# wifiweatherguy.net
KiCad netlist of a schematic drawn in EAGLE
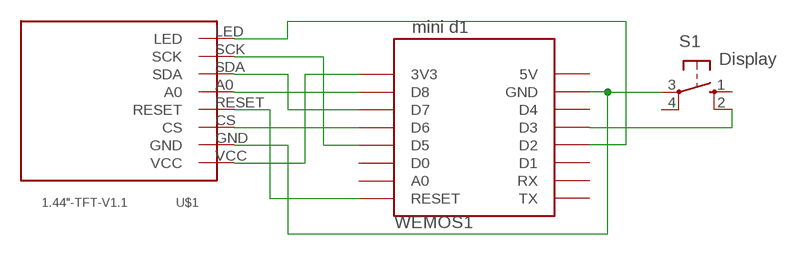
[diagram p0: schematic, sheet 1]

(export (version "E")
  (design (tool "Eeschema 10.0.6"))
  (components
    (comp (ref "S1")
      (value "Display")
      (footprint "eagle-import:B3F-10XX")
      (fields (field (name "MPN") "B3F-1000"))
      (libsource (lib "eagle-import") (part "10-XX"))
    )
    (comp (ref "U$1")
      (value "1.44\"-TFT-V1.1")
      (footprint "eagle-import:1.44-TFT-V1.1")
      (libsource (lib "eagle-import") (part "1.44{dblquote}-TFT-V1.1"))
    )
    (comp (ref "WEMOS1")
      (value "mini d1")
      (footprint "eagle-import:WEMOS-D1-MINI")
      (libsource (lib "eagle-import") (part "WEMOS-D1-MINI"))
    )
  )
  (nets
    (net (code "1") (name "Net-(S1-P)") (class "Default")
      (node (ref "S1") (pin "3") (pinfunction "P_3") (pintype "passive"))
      (node (ref "U$1") (pin "GND") (pinfunction "GND_GND") (pintype "bidirectional"))
      (node (ref "WEMOS1") (pin "GND") (pinfunction "GND_GND") (pintype "bidirectional"))
    )
    (net (code "2") (name "Net-(S1-S1)") (class "Default")
      (node (ref "S1") (pin "2") (pinfunction "S1_2") (pintype "passive"))
      (node (ref "WEMOS1") (pin "D3") (pinfunction "D3_D3") (pintype "bidirectional"))
    )
    (net (code "3") (name "Net-(U$1-PadA0)") (class "Default")
      (node (ref "U$1") (pin "A0") (pinfunction "A0_A0") (pintype "bidirectional"))
      (node (ref "WEMOS1") (pin "D8") (pinfunction "D8_D8") (pintype "bidirectional"))
    )
    (net (code "4") (name "Net-(U$1-PadCS)") (class "Default")
      (node (ref "U$1") (pin "CS") (pinfunction "CS_CS") (pintype "bidirectional"))
      (node (ref "WEMOS1") (pin "D6") (pinfunction "D6_D6") (pintype "bidirectional"))
    )
    (net (code "5") (name "Net-(U$1-PadLED)") (class "Default")
      (node (ref "U$1") (pin "LED") (pinfunction "LED_LED") (pintype "bidirectional"))
      (node (ref "WEMOS1") (pin "D2") (pinfunction "D2_D2") (pintype "bidirectional"))
    )
    (net (code "6") (name "Net-(U$1-PadRESET)") (class "Default")
      (node (ref "U$1") (pin "RESET") (pinfunction "RESET_RESET") (pintype "bidirectional"))
      (node (ref "WEMOS1") (pin "RESET") (pinfunction "RESET_RESET") (pintype "bidirectional"))
    )
    (net (code "7") (name "Net-(U$1-PadSCK)") (class "Default")
      (node (ref "U$1") (pin "SCK") (pinfunction "SCK_SCK") (pintype "bidirectional"))
      (node (ref "WEMOS1") (pin "D5") (pinfunction "D5_D5") (pintype "bidirectional"))
    )
    (net (code "8") (name "Net-(U$1-PadSDA)") (class "Default")
      (node (ref "U$1") (pin "SDA") (pinfunction "SDA_SDA") (pintype "bidirectional"))
      (node (ref "WEMOS1") (pin "D7") (pinfunction "D7_D7") (pintype "bidirectional"))
    )
    (net (code "9") (name "Net-(U$1-PadVCC)") (class "Default")
      (node (ref "U$1") (pin "VCC") (pinfunction "VCC_VCC") (pintype "bidirectional"))
      (node (ref "WEMOS1") (pin "3V3") (pinfunction "3V3_3V3") (pintype "bidirectional"))
    )
    (net (code "10") (name "unconnected-(S1-P1-Pad4)") (class "Default")
      (node (ref "S1") (pin "4") (pinfunction "P1_4") (pintype "passive"))
    )
    (net (code "11") (name "unconnected-(S1-S-Pad1)") (class "Default")
      (node (ref "S1") (pin "1") (pinfunction "S_1") (pintype "passive"))
    )
    (net (code "12") (name "unconnected-(WEMOS1-Pad5V)") (class "Default")
      (node (ref "WEMOS1") (pin "5V") (pinfunction "5V_5V") (pintype "bidirectional"))
    )
    (net (code "13") (name "unconnected-(WEMOS1-PadA0)") (class "Default")
      (node (ref "WEMOS1") (pin "A0") (pinfunction "A0_A0") (pintype "bidirectional"))
    )
    (net (code "14") (name "unconnected-(WEMOS1-PadD0)") (class "Default")
      (node (ref "WEMOS1") (pin "D0") (pinfunction "D0_D0") (pintype "bidirectional"))
    )
    (net (code "15") (name "unconnected-(WEMOS1-PadD1)") (class "Default")
      (node (ref "WEMOS1") (pin "D1") (pinfunction "D1_D1") (pintype "bidirectional"))
    )
    (net (code "16") (name "unconnected-(WEMOS1-PadD4)") (class "Default")
      (node (ref "WEMOS1") (pin "D4") (pinfunction "D4_D4") (pintype "bidirectional"))
    )
    (net (code "17") (name "unconnected-(WEMOS1-PadRX)") (class "Default")
      (node (ref "WEMOS1") (pin "RX") (pinfunction "RX_RX") (pintype "bidirectional"))
    )
    (net (code "18") (name "unconnected-(WEMOS1-PadTX)") (class "Default")
      (node (ref "WEMOS1") (pin "TX") (pinfunction "TX_TX") (pintype "bidirectional"))
    )
  )
)
